# MCU_Power_Supply_Accel.net
KiCad netlist of a schematic drawn in Altium Designer
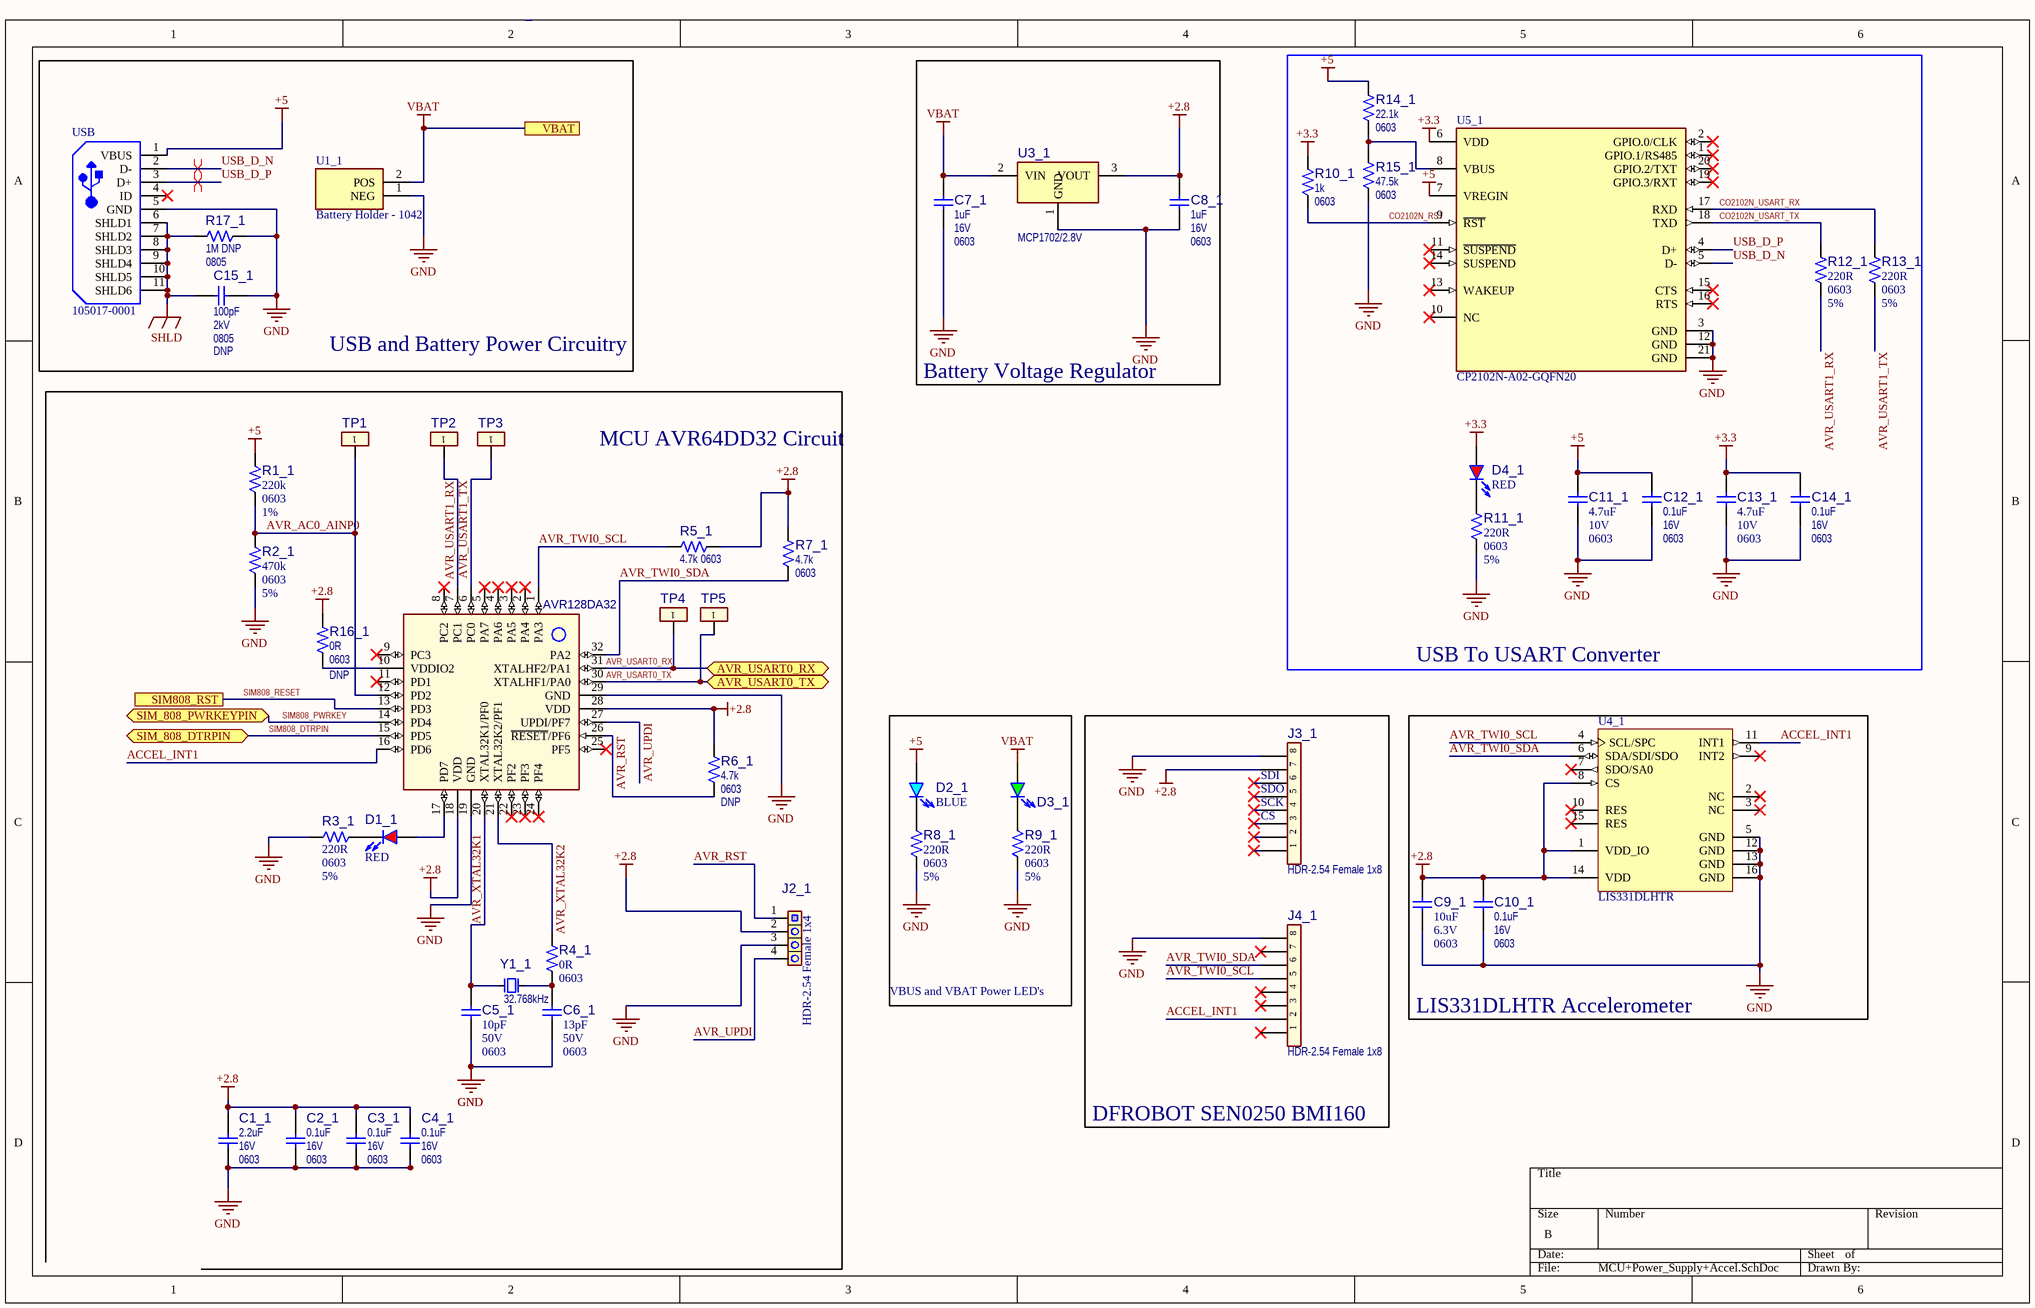
[diagram p0: MCU+Power_Supply+Accel.SchDoc]

(export (version "E")
  (design (tool "Eeschema 10.0.6"))
  (components
    (comp (ref "AVR128DA32")
      (value "AVR128DA32-E/PT")
      (footprint "TQFP-32_7x7")
      (fields (field (name "OWNER") "Simen Tanbergmoen"))
      (libsource (lib "MCHP-CDB-Offline") (part "AVR64DD32 TQFP-32"))
    )
    (comp (ref "C1_1")
      (value "2.2uF")
      (footprint "CAP_C_0603")
      (fields
        (field (name "VOLTAGE") "16V")
        (field (name "PACKAGE") "0603")
        (field (name "TOLERANCE") "10%")
        (field (name "Comment") "Capacitor NP")
      )
      (libsource (lib "MCHP-CDB") (part "Capacitor NP"))
    )
    (comp (ref "C2_1")
      (value "0.1uF")
      (footprint "CAP_C_0603")
      (fields
        (field (name "VOLTAGE") "16V")
        (field (name "PACKAGE") "0603")
        (field (name "TOLERANCE") "10%")
        (field (name "Comment") "Capacitor NP")
        (field (name "OWNER") "Cristian Papuc")
      )
      (libsource (lib "MCHP-CDB") (part "Capacitor NP"))
    )
    (comp (ref "C3_1")
      (value "0.1uF")
      (footprint "CAP_C_0603")
      (fields
        (field (name "VOLTAGE") "16V")
        (field (name "PACKAGE") "0603")
        (field (name "TOLERANCE") "10%")
        (field (name "Comment") "Capacitor NP")
        (field (name "OWNER") "Cristian Papuc")
      )
      (libsource (lib "MCHP-CDB") (part "Capacitor NP"))
    )
    (comp (ref "C4_1")
      (value "0.1uF")
      (footprint "CAP_C_0603")
      (fields
        (field (name "VOLTAGE") "16V")
        (field (name "PACKAGE") "0603")
        (field (name "TOLERANCE") "10%")
        (field (name "Comment") "Capacitor NP")
        (field (name "OWNER") "Cristian Papuc")
      )
      (libsource (lib "MCHP-CDB") (part "Capacitor NP"))
    )
    (comp (ref "C5_1")
      (value "10pF")
      (footprint "CAP_C_0603")
      (fields
        (field (name "VOLTAGE") "50V")
        (field (name "PACKAGE") "0603")
        (field (name "TOLERANCE") "5%")
        (field (name "Comment") "Capacitor NP")
        (field (name "OWNER") "Cristina Salanti")
      )
      (libsource (lib "MCHP-CDB") (part "Capacitor NP"))
    )
    (comp (ref "C6_1")
      (value "13pF")
      (footprint "CAP_C_0603")
      (fields
        (field (name "VOLTAGE") "50V")
        (field (name "PACKAGE") "0603")
        (field (name "TOLERANCE") "2%")
        (field (name "Comment") "Capacitor NP")
        (field (name "OWNER") "Dragos Danaila")
      )
      (libsource (lib "MCHP-CDB") (part "Capacitor NP"))
    )
    (comp (ref "C7_1")
      (value "1uF")
      (footprint "CAP_C_0603")
      (fields
        (field (name "VOLTAGE") "16V")
        (field (name "PACKAGE") "0603")
        (field (name "TOLERANCE") "10%")
        (field (name "Comment") "Capacitor NP")
      )
      (libsource (lib "MCHP-CDB") (part "Capacitor NP"))
    )
    (comp (ref "C8_1")
      (value "1uF")
      (footprint "CAP_C_0603")
      (fields
        (field (name "VOLTAGE") "16V")
        (field (name "PACKAGE") "0603")
        (field (name "TOLERANCE") "10%")
        (field (name "Comment") "Capacitor NP")
      )
      (libsource (lib "MCHP-CDB") (part "Capacitor NP"))
    )
    (comp (ref "C9_1")
      (value "10uF")
      (footprint "CAP_C_0603")
      (fields
        (field (name "VOLTAGE") "6.3V")
        (field (name "PACKAGE") "0603")
        (field (name "TOLERANCE") "20%")
        (field (name "Comment") "Capacitor NP")
      )
      (libsource (lib "MCHP-CDB") (part "Capacitor NP"))
    )
    (comp (ref "C10_1")
      (value "0.1uF")
      (footprint "CAP_C_0603")
      (fields
        (field (name "VOLTAGE") "16V")
        (field (name "PACKAGE") "0603")
        (field (name "TOLERANCE") "10%")
        (field (name "Comment") "Capacitor NP")
        (field (name "OWNER") "Cristian Papuc")
      )
      (libsource (lib "MCHP-CDB") (part "Capacitor NP"))
    )
    (comp (ref "C11_1")
      (value "4.7uF")
      (footprint "CAP_C_0603")
      (fields
        (field (name "VOLTAGE") "10V")
        (field (name "PACKAGE") "0603")
        (field (name "TOLERANCE") "80%")
        (field (name "Comment") "Capacitor NP")
      )
      (libsource (lib "MCHP-CDB") (part "Capacitor NP"))
    )
    (comp (ref "C12_1")
      (value "0.1uF")
      (footprint "CAP_C_0603")
      (fields
        (field (name "VOLTAGE") "16V")
        (field (name "PACKAGE") "0603")
        (field (name "TOLERANCE") "10%")
        (field (name "Comment") "Capacitor NP")
        (field (name "OWNER") "Cristian Papuc")
      )
      (libsource (lib "MCHP-CDB") (part "Capacitor NP"))
    )
    (comp (ref "C13_1")
      (value "4.7uF")
      (footprint "CAP_C_0603")
      (fields
        (field (name "VOLTAGE") "10V")
        (field (name "PACKAGE") "0603")
        (field (name "TOLERANCE") "80%")
        (field (name "Comment") "Capacitor NP")
      )
      (libsource (lib "MCHP-CDB") (part "Capacitor NP"))
    )
    (comp (ref "C14_1")
      (value "0.1uF")
      (footprint "CAP_C_0603")
      (fields
        (field (name "VOLTAGE") "16V")
        (field (name "PACKAGE") "0603")
        (field (name "TOLERANCE") "10%")
        (field (name "Comment") "Capacitor NP")
        (field (name "OWNER") "Cristian Papuc")
      )
      (libsource (lib "MCHP-CDB") (part "Capacitor NP"))
    )
    (comp (ref "C15_1")
      (value "100pF")
      (footprint "CAP_C_0805")
      (fields
        (field (name "VOLTAGE") "2kV")
        (field (name "PACKAGE") "0805")
        (field (name "TOLERANCE") "5%")
        (field (name "POPULATED") "DNP")
        (field (name "Comment") "Capacitor NP")
        (field (name "OWNER") "Cristian Papuc")
      )
      (libsource (lib "MCHP-CDB") (part "Capacitor NP"))
    )
    (comp (ref "D1_1")
      (value "RED")
      (footprint "LED_0603_RED")
      (description "LED")
      (fields (field (name "POWER") "100mW") (field (name "Comment") "LED_red"))
      (libsource (lib "MCHP-CDB") (part "LED_red"))
    )
    (comp (ref "D2_1")
      (value "BLUE")
      (footprint "LED_0603_Blue")
      (description "LED")
      (fields
        (field (name "POWER") "76mW")
        (field (name "Comment") "LED_blue")
        (field (name "OWNER") "Tad Ahlvers")
      )
      (libsource (lib "MCHP-CDB") (part "LED_blue"))
    )
    (comp (ref "D3_1")
      (value "LED_green_true")
      (footprint "LED_0603_Green")
      (description "LED TRUE GREEN")
      (fields (field (name "OWNER") "Ed Kennedy"))
      (libsource (lib "MCHP-CDB") (part "LED_green_true"))
    )
    (comp (ref "D4_1")
      (value "RED")
      (footprint "LED_0603_RED")
      (description "LED")
      (fields (field (name "POWER") "100mW") (field (name "Comment") "LED_red"))
      (libsource (lib "MCHP-CDB") (part "LED_red"))
    )
    (comp (ref "J2_1")
      (value "HDR-2.54 Female 1x4")
      (footprint "HDR_F_2.54_1x4_U_TH_V_SAM_SSW-104-01-G-S")
      (fields (field (name "Comment") "Header 1x4") (field (name "OWNER") "Randolph Sobrepena"))
      (libsource (lib "MCHP-CDB") (part "Header 1x4"))
    )
    (comp (ref "J3_1")
      (value "HDR-2.54 Female 1x8")
      (footprint "HDR_F_2.54_1x8")
      (description "Header 1x8")
      (fields (field (name "OWNER") "Bogdan P (M91398)"))
      (libsource (lib "MCHP-CDB") (part "Header 1x8"))
    )
    (comp (ref "J4_1")
      (value "HDR-2.54 Female 1x8")
      (footprint "HDR_F_2.54_1x8")
      (description "Header 1x8")
      (fields (field (name "OWNER") "Bogdan P (M91398)"))
      (libsource (lib "MCHP-CDB") (part "Header 1x8"))
    )
    (comp (ref "R1_1")
      (value "220k")
      (footprint "RES_C_0603")
      (description "Resistor")
      (fields
        (field (name "PACKAGE") "0603")
        (field (name "TOLERANCE") "1%")
        (field (name "VOLTAGE") "75V")
        (field (name "POWER") "1/10W")
        (field (name "OWNER") "Adrian M (M91404)")
      )
      (libsource (lib "MCHP-CDB") (part "Resistor"))
    )
    (comp (ref "R2_1")
      (value "470k")
      (footprint "RES_C_0603")
      (description "Resistor")
      (fields
        (field (name "PACKAGE") "0603")
        (field (name "TOLERANCE") "5%")
        (field (name "VOLTAGE") "75V")
        (field (name "POWER") "1/10W")
        (field (name "OWNER") "Adrian T (M91397)")
      )
      (libsource (lib "MCHP-CDB") (part "Resistor"))
    )
    (comp (ref "R3_1")
      (value "220R")
      (footprint "RES_C_0603")
      (description "Resistor")
      (fields
        (field (name "PACKAGE") "0603")
        (field (name "TOLERANCE") "5%")
        (field (name "VOLTAGE") "50V")
        (field (name "POWER") "1/10W")
      )
      (libsource (lib "MCHP-CDB") (part "Resistor"))
    )
    (comp (ref "R4_1")
      (value "0R")
      (footprint "RES_C_0603")
      (description "Resistor")
      (fields
        (field (name "PACKAGE") "0603")
        (field (name "POWER") "1/10W")
        (field (name "OWNER") "Steve Dziaba")
      )
      (libsource (lib "MCHP-CDB") (part "Resistor"))
    )
    (comp (ref "R5_1")
      (value "4.7k")
      (footprint "RES_C_0603")
      (description "Resistor")
      (fields
        (field (name "PACKAGE") "0603")
        (field (name "VOLTAGE") "75V")
        (field (name "POWER") "1/10W")
        (field (name "OWNER") "Bogdan P (M91398)")
      )
      (libsource (lib "MCHP-CDB") (part "Resistor"))
    )
    (comp (ref "R6_1")
      (value "4.7k")
      (footprint "RES_C_0603")
      (description "Resistor")
      (fields
        (field (name "PACKAGE") "0603")
        (field (name "VOLTAGE") "75V")
        (field (name "POWER") "1/10W")
        (field (name "POPULATED") "DNP")
        (field (name "OWNER") "Bogdan P (M91398)")
      )
      (libsource (lib "MCHP-CDB") (part "Resistor"))
    )
    (comp (ref "R7_1")
      (value "4.7k")
      (footprint "RES_C_0603")
      (description "Resistor")
      (fields
        (field (name "PACKAGE") "0603")
        (field (name "VOLTAGE") "75V")
        (field (name "POWER") "1/10W")
        (field (name "OWNER") "Bogdan P (M91398)")
      )
      (libsource (lib "MCHP-CDB") (part "Resistor"))
    )
    (comp (ref "R8_1")
      (value "220R")
      (footprint "RES_C_0603")
      (description "Resistor")
      (fields
        (field (name "PACKAGE") "0603")
        (field (name "TOLERANCE") "5%")
        (field (name "VOLTAGE") "50V")
        (field (name "POWER") "1/10W")
      )
      (libsource (lib "MCHP-CDB") (part "Resistor"))
    )
    (comp (ref "R9_1")
      (value "220R")
      (footprint "RES_C_0603")
      (description "Resistor")
      (fields
        (field (name "PACKAGE") "0603")
        (field (name "TOLERANCE") "5%")
        (field (name "VOLTAGE") "50V")
        (field (name "POWER") "1/10W")
      )
      (libsource (lib "MCHP-CDB") (part "Resistor"))
    )
    (comp (ref "R10_1")
      (value "1k")
      (footprint "RES_C_0603")
      (description "Resistor")
      (fields
        (field (name "PACKAGE") "0603")
        (field (name "VOLTAGE") "75V")
        (field (name "POWER") "1/10W")
        (field (name "OWNER") "Tad Ahlvers")
      )
      (libsource (lib "MCHP-CDB") (part "Resistor"))
    )
    (comp (ref "R11_1")
      (value "220R")
      (footprint "RES_C_0603")
      (description "Resistor")
      (fields
        (field (name "PACKAGE") "0603")
        (field (name "TOLERANCE") "5%")
        (field (name "VOLTAGE") "50V")
        (field (name "POWER") "1/10W")
      )
      (libsource (lib "MCHP-CDB") (part "Resistor"))
    )
    (comp (ref "R12_1")
      (value "220R")
      (footprint "RES_C_0603")
      (description "Resistor")
      (fields
        (field (name "PACKAGE") "0603")
        (field (name "TOLERANCE") "5%")
        (field (name "VOLTAGE") "50V")
        (field (name "POWER") "1/10W")
      )
      (libsource (lib "MCHP-CDB") (part "Resistor"))
    )
    (comp (ref "R13_1")
      (value "220R")
      (footprint "RES_C_0603")
      (description "Resistor")
      (fields
        (field (name "PACKAGE") "0603")
        (field (name "TOLERANCE") "5%")
        (field (name "VOLTAGE") "50V")
        (field (name "POWER") "1/10W")
      )
      (libsource (lib "MCHP-CDB") (part "Resistor"))
    )
    (comp (ref "R14_1")
      (value "22.1k")
      (footprint "RES_C_0603")
      (description "Resistor")
      (fields
        (field (name "PACKAGE") "0603")
        (field (name "VOLTAGE") "75V")
        (field (name "POWER") "1/10W")
        (field (name "OWNER") "Kamatchi Sundaresan")
      )
      (libsource (lib "MCHP-CDB") (part "Resistor"))
    )
    (comp (ref "R15_1")
      (value "47.5k")
      (footprint "RES_C_0603")
      (description "Resistor")
      (fields
        (field (name "PACKAGE") "0603")
        (field (name "POWER") "1/10W")
        (field (name "OWNER") "Sam Charles")
      )
      (libsource (lib "MCHP-CDB") (part "Resistor"))
    )
    (comp (ref "R16_1")
      (value "0R")
      (footprint "RES_C_0603")
      (description "Resistor")
      (fields
        (field (name "PACKAGE") "0603")
        (field (name "POWER") "1/10W")
        (field (name "POPULATED") "DNP")
        (field (name "OWNER") "Steve Dziaba")
      )
      (libsource (lib "MCHP-CDB") (part "Resistor"))
    )
    (comp (ref "R17_1")
      (value "1M")
      (footprint "RES_C_0805")
      (description "Resistor")
      (fields
        (field (name "PACKAGE") "0805")
        (field (name "VOLTAGE") "100V")
        (field (name "POWER") "1/8W")
        (field (name "POPULATED") "DNP")
      )
      (libsource (lib "MCHP-CDB") (part "Resistor"))
    )
    (comp (ref "TP1")
      (value "Header 1x1")
      (footprint "HDR_M_2.54_1x1")
      (fields (field (name "VOLTAGE") "550VAC"))
      (libsource (lib "MCHP-CDB") (part "Header 1x1"))
    )
    (comp (ref "TP2")
      (value "Header 1x1")
      (footprint "HDR_M_2.54_1x1")
      (fields (field (name "VOLTAGE") "550VAC"))
      (libsource (lib "MCHP-CDB") (part "Header 1x1"))
    )
    (comp (ref "TP3")
      (value "Header 1x1")
      (footprint "HDR_M_2.54_1x1")
      (fields (field (name "VOLTAGE") "550VAC"))
      (libsource (lib "MCHP-CDB") (part "Header 1x1"))
    )
    (comp (ref "TP4")
      (value "Header 1x1")
      (footprint "HDR_M_2.54_1x1")
      (fields (field (name "VOLTAGE") "550VAC"))
      (libsource (lib "MCHP-CDB") (part "Header 1x1"))
    )
    (comp (ref "TP5")
      (value "Header 1x1")
      (footprint "HDR_M_2.54_1x1")
      (fields (field (name "VOLTAGE") "550VAC"))
      (libsource (lib "MCHP-CDB") (part "Header 1x1"))
    )
    (comp (ref "U1_1")
      (value "Battery Holder - 1042")
      (footprint "SamacSys:KEYSTONE-1042")
      (description "Undefined or Miscellaneous")
      (fields (field (name "MANUFACTURER_PART_NUMBER") "1042") (field (name "MOUSER PART NUMBER") "534-1042"))
      (libsource (lib "*") (part "1042"))
    )
    (comp (ref "U3_1")
      (value "MCP1702/2.8V")
      (footprint "SOT-89-3")
      (description "LDO")
      (fields (field (name "Comment") "MCP170X SOT-89-3_TO-92-3"))
      (libsource (lib "MCHP-CDB") (part "MCP170X SOT-89-3_TO-92-3"))
    )
    (comp (ref "U4_1")
      (value "LIS331DLHTR")
      (footprint "STM-LGA16-3X3X1")
      (fields (field (name "MANUFACTURER") "STMicroelectronics"))
      (libsource (lib "Altium Content Vault") (part "SEN-MOT-LIS331DL-16"))
    )
    (comp (ref "U5_1")
      (value "CP2102N-A02-GQFN20")
      (footprint "FP-CP2102N-A02-GQFN20-MFG")
      (description "IC USB TO UART BRIDGE QFN20")
      (libsource (lib "Altium Content Vault") (part "535e9eb0fa6e07ebb008498c6833ade"))
    )
    (comp (ref "USB")
      (value "105017-0001")
      (footprint "USB-MICRO-B_V")
      (fields (field (name "MANUFACTURER") "Molex"))
      (libsource (lib "Altium Content Vault") (part "USB-5-6SHLD"))
    )
    (comp (ref "Y1_1")
      (value "32.768kHz")
      (footprint "CRYSTAL_FX135A_L3.2W1.5H0.9")
      (description "Crystal")
      (fields
        (field (name "TOLERANCE") "20ppm")
        (field (name "Comment") "Crystal 2 Pins")
        (field (name "OWNER") "Jesus Aviles")
      )
      (libsource (lib "MCHP-CDB") (part "Crystal 2 Pins"))
    )
  )
  (nets
    (net (code "1") (name "+2.8") (class "Default")
      (node (ref "AVR128DA32") (pin "18") (pinfunction "VDD_18") (pintype "power_in"))
      (node (ref "AVR128DA32") (pin "28") (pinfunction "VDD_28") (pintype "power_in"))
      (node (ref "C10_1") (pin "2") (pinfunction "2_2") (pintype "passive"))
      (node (ref "C1_1") (pin "2") (pinfunction "2_2") (pintype "passive"))
      (node (ref "C2_1") (pin "2") (pinfunction "2_2") (pintype "passive"))
      (node (ref "C3_1") (pin "2") (pinfunction "2_2") (pintype "passive"))
      (node (ref "C4_1") (pin "2") (pinfunction "2_2") (pintype "passive"))
      (node (ref "C8_1") (pin "2") (pinfunction "2_2") (pintype "passive"))
      (node (ref "C9_1") (pin "2") (pinfunction "2_2") (pintype "passive"))
      (node (ref "J2_1") (pin "2") (pinfunction "2_2") (pintype "passive"))
      (node (ref "J3_1") (pin "7") (pinfunction "7_7") (pintype "passive"))
      (node (ref "R16_1") (pin "1") (pinfunction "1_1") (pintype "passive"))
      (node (ref "R5_1") (pin "2") (pinfunction "2_2") (pintype "passive"))
      (node (ref "R6_1") (pin "2") (pinfunction "2_2") (pintype "passive"))
      (node (ref "R7_1") (pin "2") (pinfunction "2_2") (pintype "passive"))
      (node (ref "U3_1") (pin "3") (pinfunction "VOUT_3") (pintype "power_in"))
      (node (ref "U4_1") (pin "1") (pinfunction "VDD_IO_1") (pintype "power_in"))
      (node (ref "U4_1") (pin "14") (pinfunction "VDD_14") (pintype "power_in"))
      (node (ref "U4_1") (pin "8") (pinfunction "CS_8") (pintype "input"))
    )
    (net (code "2") (name "+3.3") (class "Default")
      (node (ref "C13_1") (pin "2") (pinfunction "2_2") (pintype "passive"))
      (node (ref "C14_1") (pin "2") (pinfunction "2_2") (pintype "passive"))
      (node (ref "D4_1") (pin "1") (pinfunction "A_1") (pintype "passive"))
      (node (ref "R10_1") (pin "2") (pinfunction "2_2") (pintype "passive"))
      (node (ref "U5_1") (pin "6") (pinfunction "VDD_6") (pintype "power_in"))
    )
    (net (code "3") (name "+5") (class "Default")
      (node (ref "C11_1") (pin "2") (pinfunction "2_2") (pintype "passive"))
      (node (ref "C12_1") (pin "2") (pinfunction "2_2") (pintype "passive"))
      (node (ref "D2_1") (pin "1") (pinfunction "A_1") (pintype "passive"))
      (node (ref "R14_1") (pin "2") (pinfunction "2_2") (pintype "passive"))
      (node (ref "R1_1") (pin "2") (pinfunction "2_2") (pintype "passive"))
      (node (ref "U5_1") (pin "7") (pinfunction "VREGIN_7") (pintype "power_in"))
      (node (ref "USB") (pin "1") (pinfunction "VBUS_1") (pintype "passive"))
    )
    (net (code "4") (name "/ACCEL_INT1") (class "Default")
      (node (ref "AVR128DA32") (pin "16") (pinfunction "PD6_16") (pintype "bidirectional"))
      (node (ref "J4_1") (pin "2") (pinfunction "2_2") (pintype "passive"))
      (node (ref "U4_1") (pin "11") (pinfunction "INT1_11") (pintype "output"))
    )
    (net (code "5") (name "/AVR_AC0_AINP0") (class "Default")
      (node (ref "AVR128DA32") (pin "12") (pinfunction "PD2_12") (pintype "bidirectional"))
      (node (ref "R1_1") (pin "1") (pinfunction "1_1") (pintype "passive"))
      (node (ref "R2_1") (pin "1") (pinfunction "1_1") (pintype "passive"))
      (node (ref "TP1") (pin "1") (pinfunction "1_1") (pintype "passive"))
    )
    (net (code "6") (name "/AVR_RST") (class "Default")
      (node (ref "AVR128DA32") (pin "26") (pinfunction "~{RESET}/PF6_26") (pintype "input"))
      (node (ref "J2_1") (pin "1") (pinfunction "1_1") (pintype "passive"))
      (node (ref "R6_1") (pin "1") (pinfunction "1_1") (pintype "passive"))
    )
    (net (code "7") (name "/AVR_TWI0_SCL") (class "Default")
      (node (ref "AVR128DA32") (pin "1") (pinfunction "PA3_1") (pintype "bidirectional"))
      (node (ref "J4_1") (pin "5") (pinfunction "5_5") (pintype "passive"))
      (node (ref "R5_1") (pin "1") (pinfunction "1_1") (pintype "passive"))
      (node (ref "U4_1") (pin "4") (pinfunction "SCL/SPC_4") (pintype "input"))
    )
    (net (code "8") (name "/AVR_TWI0_SDA") (class "Default")
      (node (ref "AVR128DA32") (pin "32") (pinfunction "PA2_32") (pintype "bidirectional"))
      (node (ref "J4_1") (pin "6") (pinfunction "6_6") (pintype "passive"))
      (node (ref "R7_1") (pin "1") (pinfunction "1_1") (pintype "passive"))
      (node (ref "U4_1") (pin "6") (pinfunction "SDA/SDI/SDO_6") (pintype "bidirectional"))
    )
    (net (code "9") (name "/AVR_UPDI") (class "Default")
      (node (ref "AVR128DA32") (pin "27") (pinfunction "UPDI/PF7_27") (pintype "bidirectional"))
      (node (ref "J2_1") (pin "4") (pinfunction "4_4") (pintype "passive"))
    )
    (net (code "10") (name "/AVR_USART0_RX") (class "Default")
      (node (ref "AVR128DA32") (pin "31") (pinfunction "XTALHF2/PA1_31") (pintype "bidirectional"))
      (node (ref "TP4") (pin "1") (pinfunction "1_1") (pintype "passive"))
    )
    (net (code "11") (name "/AVR_USART0_TX") (class "Default")
      (node (ref "AVR128DA32") (pin "30") (pinfunction "XTALHF1/PA0_30") (pintype "bidirectional"))
      (node (ref "TP5") (pin "1") (pinfunction "1_1") (pintype "passive"))
    )
    (net (code "12") (name "/AVR_USART1_RX") (class "Default")
      (node (ref "AVR128DA32") (pin "7") (pinfunction "PC1_7") (pintype "bidirectional"))
      (node (ref "R12_1") (pin "1") (pinfunction "1_1") (pintype "passive"))
      (node (ref "TP2") (pin "1") (pinfunction "1_1") (pintype "passive"))
    )
    (net (code "13") (name "/AVR_USART1_TX") (class "Default")
      (node (ref "AVR128DA32") (pin "6") (pinfunction "PC0_6") (pintype "bidirectional"))
      (node (ref "R13_1") (pin "1") (pinfunction "1_1") (pintype "passive"))
      (node (ref "TP3") (pin "1") (pinfunction "1_1") (pintype "passive"))
    )
    (net (code "14") (name "/AVR_XTAL32K1") (class "Default")
      (node (ref "AVR128DA32") (pin "20") (pinfunction "XTAL32K1/PF0_20") (pintype "bidirectional"))
      (node (ref "C5_1") (pin "2") (pinfunction "2_2") (pintype "passive"))
      (node (ref "Y1_1") (pin "1") (pinfunction "Osc1_1") (pintype "passive"))
    )
    (net (code "15") (name "/AVR_XTAL32K2") (class "Default")
      (node (ref "AVR128DA32") (pin "21") (pinfunction "XTAL32K2/PF1_21") (pintype "bidirectional"))
      (node (ref "R4_1") (pin "2") (pinfunction "2_2") (pintype "passive"))
    )
    (net (code "16") (name "/CO2102N_RST") (class "Default")
      (node (ref "R10_1") (pin "1") (pinfunction "1_1") (pintype "passive"))
      (node (ref "U5_1") (pin "9") (pinfunction "~{RST}_9") (pintype "input"))
    )
    (net (code "17") (name "/CO2102N_USART_RX") (class "Default")
      (node (ref "R13_1") (pin "2") (pinfunction "2_2") (pintype "passive"))
      (node (ref "U5_1") (pin "17") (pinfunction "RXD_17") (pintype "input"))
    )
    (net (code "18") (name "/CO2102N_USART_TX") (class "Default")
      (node (ref "R12_1") (pin "2") (pinfunction "2_2") (pintype "passive"))
      (node (ref "U5_1") (pin "18") (pinfunction "TXD_18") (pintype "output"))
    )
    (net (code "19") (name "/SIM808_DTRPIN") (class "Default")
      (node (ref "AVR128DA32") (pin "15") (pinfunction "PD5_15") (pintype "bidirectional"))
    )
    (net (code "20") (name "/SIM808_PWRKEY") (class "Default")
      (node (ref "AVR128DA32") (pin "14") (pinfunction "PD4_14") (pintype "bidirectional"))
    )
    (net (code "21") (name "/SIM808_RESET") (class "Default")
      (node (ref "AVR128DA32") (pin "13") (pinfunction "PD3_13") (pintype "bidirectional"))
    )
    (net (code "22") (name "/USB_D_N") (class "Default")
      (node (ref "U5_1") (pin "5") (pinfunction "D-_5") (pintype "bidirectional"))
      (node (ref "USB") (pin "2") (pinfunction "D-_2") (pintype "passive"))
    )
    (net (code "23") (name "/USB_D_P") (class "Default")
      (node (ref "U5_1") (pin "4") (pinfunction "D+_4") (pintype "bidirectional"))
      (node (ref "USB") (pin "3") (pinfunction "D+_3") (pintype "passive"))
    )
    (net (code "24") (name "GND") (class "Default")
      (node (ref "AVR128DA32") (pin "19") (pinfunction "GND_19") (pintype "power_in"))
      (node (ref "AVR128DA32") (pin "29") (pinfunction "GND_29") (pintype "power_in"))
      (node (ref "C10_1") (pin "1") (pinfunction "1_1") (pintype "passive"))
      (node (ref "C11_1") (pin "1") (pinfunction "1_1") (pintype "passive"))
      (node (ref "C12_1") (pin "1") (pinfunction "1_1") (pintype "passive"))
      (node (ref "C13_1") (pin "1") (pinfunction "1_1") (pintype "passive"))
      (node (ref "C14_1") (pin "1") (pinfunction "1_1") (pintype "passive"))
      (node (ref "C15_1") (pin "2") (pinfunction "2_2") (pintype "passive"))
      (node (ref "C1_1") (pin "1") (pinfunction "1_1") (pintype "passive"))
      (node (ref "C2_1") (pin "1") (pinfunction "1_1") (pintype "passive"))
      (node (ref "C3_1") (pin "1") (pinfunction "1_1") (pintype "passive"))
      (node (ref "C4_1") (pin "1") (pinfunction "1_1") (pintype "passive"))
      (node (ref "C5_1") (pin "1") (pinfunction "1_1") (pintype "passive"))
      (node (ref "C6_1") (pin "1") (pinfunction "1_1") (pintype "passive"))
      (node (ref "C7_1") (pin "1") (pinfunction "1_1") (pintype "passive"))
      (node (ref "C8_1") (pin "1") (pinfunction "1_1") (pintype "passive"))
      (node (ref "C9_1") (pin "1") (pinfunction "1_1") (pintype "passive"))
      (node (ref "J2_1") (pin "3") (pinfunction "3_3") (pintype "passive"))
      (node (ref "J3_1") (pin "8") (pinfunction "8_8") (pintype "passive"))
      (node (ref "J4_1") (pin "8") (pinfunction "8_8") (pintype "passive"))
      (node (ref "R11_1") (pin "1") (pinfunction "1_1") (pintype "passive"))
      (node (ref "R15_1") (pin "1") (pinfunction "1_1") (pintype "passive"))
      (node (ref "R17_1") (pin "2") (pinfunction "2_2") (pintype "passive"))
      (node (ref "R2_1") (pin "2") (pinfunction "2_2") (pintype "passive"))
      (node (ref "R3_1") (pin "2") (pinfunction "2_2") (pintype "passive"))
      (node (ref "R8_1") (pin "1") (pinfunction "1_1") (pintype "passive"))
      (node (ref "R9_1") (pin "1") (pinfunction "1_1") (pintype "passive"))
      (node (ref "U1_1") (pin "1") (pinfunction "NEG_1") (pintype "passive"))
      (node (ref "U3_1") (pin "1") (pinfunction "GND_1") (pintype "power_in"))
      (node (ref "U4_1") (pin "12") (pinfunction "GND_12") (pintype "power_in"))
      (node (ref "U4_1") (pin "13") (pinfunction "GND_13") (pintype "power_in"))
      (node (ref "U4_1") (pin "16") (pinfunction "GND_16") (pintype "power_in"))
      (node (ref "U4_1") (pin "5") (pinfunction "GND_5") (pintype "power_in"))
      (node (ref "U5_1") (pin "12") (pinfunction "GND_12") (pintype "power_in"))
      (node (ref "U5_1") (pin "21") (pinfunction "GND_21") (pintype "power_in"))
      (node (ref "U5_1") (pin "3") (pinfunction "GND_3") (pintype "power_in"))
      (node (ref "USB") (pin "5") (pinfunction "GND_5") (pintype "passive"))
    )
    (net (code "25") (name "Net-(AVR128DA32-PD7)") (class "Default")
      (node (ref "AVR128DA32") (pin "17") (pinfunction "PD7_17") (pintype "bidirectional"))
      (node (ref "D1_1") (pin "1") (pinfunction "A_1") (pintype "passive"))
    )
    (net (code "26") (name "Net-(AVR128DA32-VDDIO2)") (class "Default")
      (node (ref "AVR128DA32") (pin "10") (pinfunction "VDDIO2_10") (pintype "power_in"))
      (node (ref "R16_1") (pin "2") (pinfunction "2_2") (pintype "passive"))
    )
    (net (code "27") (name "Net-(D1_1-K)") (class "Default")
      (node (ref "D1_1") (pin "2") (pinfunction "K_2") (pintype "passive"))
      (node (ref "R3_1") (pin "1") (pinfunction "1_1") (pintype "passive"))
    )
    (net (code "28") (name "Net-(D2_1-K)") (class "Default")
      (node (ref "D2_1") (pin "2") (pinfunction "K_2") (pintype "passive"))
      (node (ref "R8_1") (pin "2") (pinfunction "2_2") (pintype "passive"))
    )
    (net (code "29") (name "Net-(D3_1-K)") (class "Default")
      (node (ref "D3_1") (pin "2") (pinfunction "K_2") (pintype "passive"))
      (node (ref "R9_1") (pin "2") (pinfunction "2_2") (pintype "passive"))
    )
    (net (code "30") (name "Net-(D4_1-K)") (class "Default")
      (node (ref "D4_1") (pin "2") (pinfunction "K_2") (pintype "passive"))
      (node (ref "R11_1") (pin "2") (pinfunction "2_2") (pintype "passive"))
    )
    (net (code "31") (name "Net-(U5_1-VBUS)") (class "Default")
      (node (ref "R14_1") (pin "1") (pinfunction "1_1") (pintype "passive"))
      (node (ref "R15_1") (pin "2") (pinfunction "2_2") (pintype "passive"))
      (node (ref "U5_1") (pin "8") (pinfunction "VBUS_8") (pintype "power_in"))
    )
    (net (code "32") (name "Net-(Y1_1-Osc2)") (class "Default")
      (node (ref "C6_1") (pin "2") (pinfunction "2_2") (pintype "passive"))
      (node (ref "R4_1") (pin "1") (pinfunction "1_1") (pintype "passive"))
      (node (ref "Y1_1") (pin "2") (pinfunction "Osc2_2") (pintype "passive"))
    )
    (net (code "33") (name "SHLD") (class "Default")
      (node (ref "C15_1") (pin "1") (pinfunction "1_1") (pintype "passive"))
      (node (ref "R17_1") (pin "1") (pinfunction "1_1") (pintype "passive"))
      (node (ref "USB") (pin "10") (pinfunction "SHLD5_10") (pintype "passive"))
      (node (ref "USB") (pin "11") (pinfunction "SHLD6_11") (pintype "passive"))
      (node (ref "USB") (pin "6") (pinfunction "SHLD1_6") (pintype "passive"))
      (node (ref "USB") (pin "7") (pinfunction "SHLD2_7") (pintype "passive"))
      (node (ref "USB") (pin "8") (pinfunction "SHLD3_8") (pintype "passive"))
      (node (ref "USB") (pin "9") (pinfunction "SHLD4_9") (pintype "passive"))
    )
    (net (code "34") (name "VBAT") (class "Default")
      (node (ref "C7_1") (pin "2") (pinfunction "2_2") (pintype "passive"))
      (node (ref "D3_1") (pin "1") (pinfunction "A_1") (pintype "passive"))
      (node (ref "U1_1") (pin "2") (pinfunction "POS_2") (pintype "passive"))
      (node (ref "U3_1") (pin "2") (pinfunction "VIN_2") (pintype "power_in"))
    )
    (net (code "35") (name "unconnected-(AVR128DA32-PA4-Pad2)") (class "Default")
      (node (ref "AVR128DA32") (pin "2") (pinfunction "PA4_2") (pintype "bidirectional+no_connect"))
    )
    (net (code "36") (name "unconnected-(AVR128DA32-PA5-Pad3)") (class "Default")
      (node (ref "AVR128DA32") (pin "3") (pinfunction "PA5_3") (pintype "bidirectional+no_connect"))
    )
    (net (code "37") (name "unconnected-(AVR128DA32-PA6-Pad4)") (class "Default")
      (node (ref "AVR128DA32") (pin "4") (pinfunction "PA6_4") (pintype "bidirectional+no_connect"))
    )
    (net (code "38") (name "unconnected-(AVR128DA32-PA7-Pad5)") (class "Default")
      (node (ref "AVR128DA32") (pin "5") (pinfunction "PA7_5") (pintype "bidirectional+no_connect"))
    )
    (net (code "39") (name "unconnected-(AVR128DA32-PC2-Pad8)") (class "Default")
      (node (ref "AVR128DA32") (pin "8") (pinfunction "PC2_8") (pintype "bidirectional+no_connect"))
    )
    (net (code "40") (name "unconnected-(AVR128DA32-PC3-Pad9)") (class "Default")
      (node (ref "AVR128DA32") (pin "9") (pinfunction "PC3_9") (pintype "bidirectional+no_connect"))
    )
    (net (code "41") (name "unconnected-(AVR128DA32-PD1-Pad11)") (class "Default")
      (node (ref "AVR128DA32") (pin "11") (pinfunction "PD1_11") (pintype "bidirectional+no_connect"))
    )
    (net (code "42") (name "unconnected-(AVR128DA32-PF2-Pad22)") (class "Default")
      (node (ref "AVR128DA32") (pin "22") (pinfunction "PF2_22") (pintype "bidirectional+no_connect"))
    )
    (net (code "43") (name "unconnected-(AVR128DA32-PF3-Pad23)") (class "Default")
      (node (ref "AVR128DA32") (pin "23") (pinfunction "PF3_23") (pintype "bidirectional+no_connect"))
    )
    (net (code "44") (name "unconnected-(AVR128DA32-PF4-Pad24)") (class "Default")
      (node (ref "AVR128DA32") (pin "24") (pinfunction "PF4_24") (pintype "bidirectional+no_connect"))
    )
    (net (code "45") (name "unconnected-(AVR128DA32-PF5-Pad25)") (class "Default")
      (node (ref "AVR128DA32") (pin "25") (pinfunction "PF5_25") (pintype "bidirectional+no_connect"))
    )
    (net (code "46") (name "unconnected-(J3_1-Pad1)") (class "Default")
      (node (ref "J3_1") (pin "1") (pinfunction "1_1") (pintype "passive+no_connect"))
    )
    (net (code "47") (name "unconnected-(J3_1-Pad2)") (class "Default")
      (node (ref "J3_1") (pin "2") (pinfunction "2_2") (pintype "passive+no_connect"))
    )
    (net (code "48") (name "unconnected-(J3_1-Pad3)") (class "Default")
      (node (ref "J3_1") (pin "3") (pinfunction "3_3") (pintype "passive+no_connect"))
    )
    (net (code "49") (name "unconnected-(J3_1-Pad4)") (class "Default")
      (node (ref "J3_1") (pin "4") (pinfunction "4_4") (pintype "passive+no_connect"))
    )
    (net (code "50") (name "unconnected-(J3_1-Pad5)") (class "Default")
      (node (ref "J3_1") (pin "5") (pinfunction "5_5") (pintype "passive+no_connect"))
    )
    (net (code "51") (name "unconnected-(J3_1-Pad6)") (class "Default")
      (node (ref "J3_1") (pin "6") (pinfunction "6_6") (pintype "passive+no_connect"))
    )
    (net (code "52") (name "unconnected-(J4_1-Pad1)") (class "Default")
      (node (ref "J4_1") (pin "1") (pinfunction "1_1") (pintype "passive+no_connect"))
    )
    (net (code "53") (name "unconnected-(J4_1-Pad3)") (class "Default")
      (node (ref "J4_1") (pin "3") (pinfunction "3_3") (pintype "passive+no_connect"))
    )
    (net (code "54") (name "unconnected-(J4_1-Pad4)") (class "Default")
      (node (ref "J4_1") (pin "4") (pinfunction "4_4") (pintype "passive+no_connect"))
    )
    (net (code "55") (name "unconnected-(J4_1-Pad7)") (class "Default")
      (node (ref "J4_1") (pin "7") (pinfunction "7_7") (pintype "passive+no_connect"))
    )
    (net (code "56") (name "unconnected-(U4_1-INT2-Pad9)") (class "Default")
      (node (ref "U4_1") (pin "9") (pinfunction "INT2_9") (pintype "output+no_connect"))
    )
    (net (code "57") (name "unconnected-(U4_1-NC-Pad2)") (class "Default")
      (node (ref "U4_1") (pin "2") (pinfunction "NC_2") (pintype "passive+no_connect"))
    )
    (net (code "58") (name "unconnected-(U4_1-NC-Pad3)") (class "Default")
      (node (ref "U4_1") (pin "3") (pinfunction "NC_3") (pintype "passive+no_connect"))
    )
    (net (code "59") (name "unconnected-(U4_1-RES-Pad10)") (class "Default")
      (node (ref "U4_1") (pin "10") (pinfunction "RES_10") (pintype "passive+no_connect"))
    )
    (net (code "60") (name "unconnected-(U4_1-RES-Pad15)") (class "Default")
      (node (ref "U4_1") (pin "15") (pinfunction "RES_15") (pintype "passive+no_connect"))
    )
    (net (code "61") (name "unconnected-(U4_1-SDO{slash}SA0-Pad7)") (class "Default")
      (node (ref "U4_1") (pin "7") (pinfunction "SDO/SA0_7") (pintype "output+no_connect"))
    )
    (net (code "62") (name "unconnected-(U5_1-CTS-Pad15)") (class "Default")
      (node (ref "U5_1") (pin "15") (pinfunction "CTS_15") (pintype "input+no_connect"))
    )
    (net (code "63") (name "unconnected-(U5_1-GPIO.0{slash}CLK-Pad2)") (class "Default")
      (node (ref "U5_1") (pin "2") (pinfunction "GPIO.0/CLK_2") (pintype "bidirectional+no_connect"))
    )
    (net (code "64") (name "unconnected-(U5_1-GPIO.1{slash}RS485-Pad1)") (class "Default")
      (node (ref "U5_1") (pin "1") (pinfunction "GPIO.1/RS485_1") (pintype "bidirectional+no_connect"))
    )
    (net (code "65") (name "unconnected-(U5_1-GPIO.2{slash}TXT-Pad20)") (class "Default")
      (node (ref "U5_1") (pin "20") (pinfunction "GPIO.2/TXT_20") (pintype "bidirectional+no_connect"))
    )
    (net (code "66") (name "unconnected-(U5_1-GPIO.3{slash}RXT-Pad19)") (class "Default")
      (node (ref "U5_1") (pin "19") (pinfunction "GPIO.3/RXT_19") (pintype "bidirectional+no_connect"))
    )
    (net (code "67") (name "unconnected-(U5_1-NC-Pad10)") (class "Default")
      (node (ref "U5_1") (pin "10") (pinfunction "NC_10") (pintype "passive+no_connect"))
    )
    (net (code "68") (name "unconnected-(U5_1-RTS-Pad16)") (class "Default")
      (node (ref "U5_1") (pin "16") (pinfunction "RTS_16") (pintype "input+no_connect"))
    )
    (net (code "69") (name "unconnected-(U5_1-SUSPEND-Pad14)") (class "Default")
      (node (ref "U5_1") (pin "14") (pinfunction "SUSPEND_14") (pintype "input+no_connect"))
    )
    (net (code "70") (name "unconnected-(U5_1-WAKEUP-Pad13)") (class "Default")
      (node (ref "U5_1") (pin "13") (pinfunction "WAKEUP_13") (pintype "input+no_connect"))
    )
    (net (code "71") (name "unconnected-(U5_1-~{SUSPEND}-Pad11)") (class "Default")
      (node (ref "U5_1") (pin "11") (pinfunction "~{SUSPEND}_11") (pintype "input+no_connect"))
    )
    (net (code "72") (name "unconnected-(USB-ID-Pad4)") (class "Default")
      (node (ref "USB") (pin "4") (pinfunction "ID_4") (pintype "passive+no_connect"))
    )
  )
)
